# thrust_stand.net
KiCad netlist of a schematic drawn in EAGLE
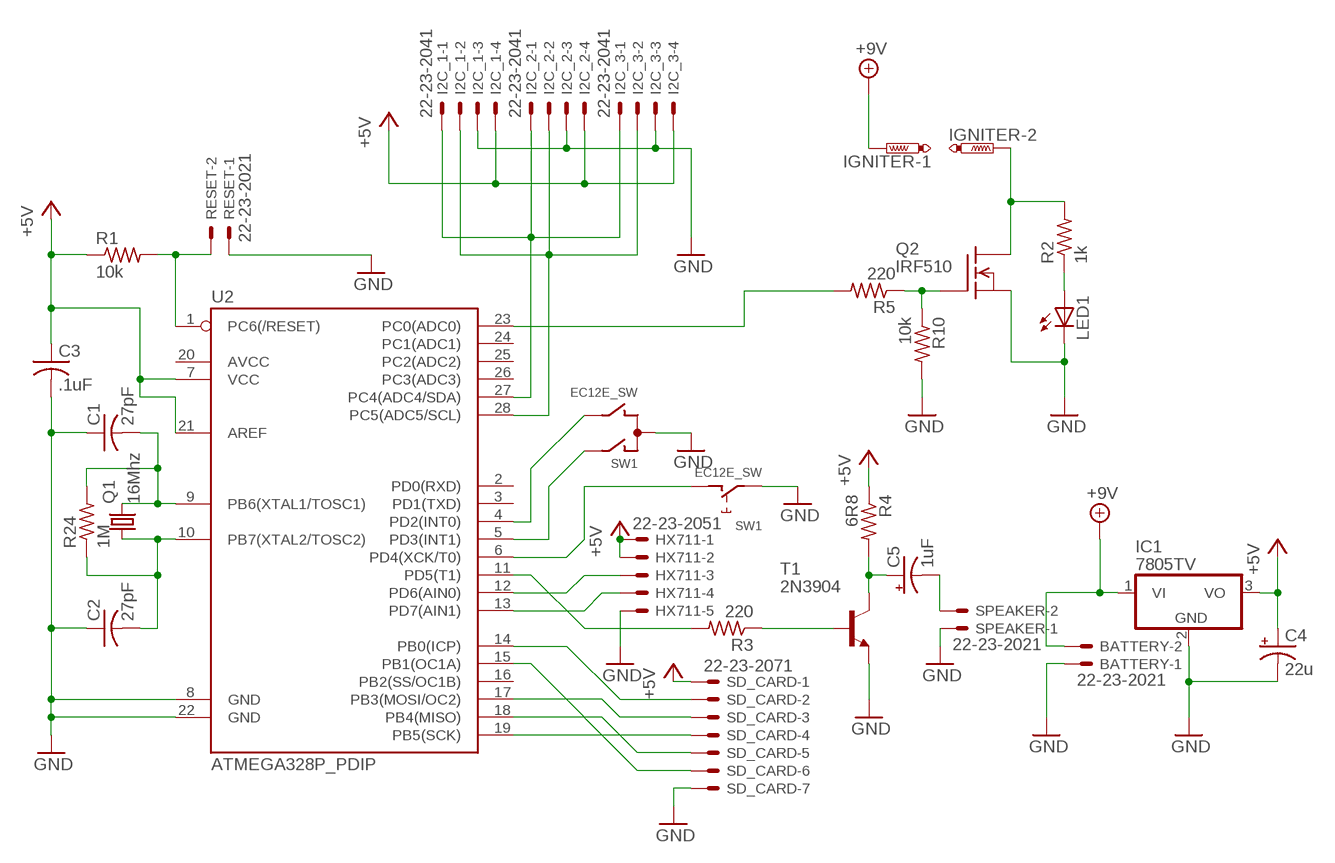
[diagram p0: schematic, sheet 1]

(export (version "E")
  (design (tool "Eeschema 10.0.6"))
  (components
    (comp (ref "BATTERY")
      (value "22-23-2021")
      (footprint "eagle-import:22-23-2021")
      (fields (field (name "MF") "MOLEX"))
      (libsource (lib "eagle-import") (part "22-23-2021"))
    )
    (comp (ref "C1")
      (value "27pF")
      (footprint "eagle-import:C025-040X050")
      (libsource (lib "eagle-import") (part "C-US025-040X050"))
    )
    (comp (ref "C2")
      (value "27pF")
      (footprint "eagle-import:C025-040X050")
      (libsource (lib "eagle-import") (part "C-US025-040X050"))
    )
    (comp (ref "C3")
      (value ".1uF")
      (footprint "eagle-import:C025-030X050")
      (libsource (lib "eagle-import") (part "C-US025-030X050"))
    )
    (comp (ref "C4")
      (value "22u")
      (footprint "eagle-import:B45181A")
      (libsource (lib "eagle-import") (part "CPOL-USB45181A"))
    )
    (comp (ref "C5")
      (value "1uF")
      (footprint "eagle-import:B45181A")
      (libsource (lib "eagle-import") (part "CPOL-USB45181A"))
    )
    (comp (ref "HX711")
      (value "22-23-2051")
      (footprint "eagle-import:22-23-2051")
      (fields (field (name "MF") "MOLEX"))
      (libsource (lib "eagle-import") (part "22-23-2051"))
    )
    (comp (ref "I2C_1")
      (value "22-23-2041")
      (footprint "eagle-import:22-23-2041")
      (fields (field (name "MF") "MOLEX"))
      (libsource (lib "eagle-import") (part "22-23-2041"))
    )
    (comp (ref "I2C_2")
      (value "22-23-2041")
      (footprint "eagle-import:22-23-2041")
      (fields (field (name "MF") "MOLEX"))
      (libsource (lib "eagle-import") (part "22-23-2041"))
    )
    (comp (ref "I2C_3")
      (value "22-23-2041")
      (footprint "eagle-import:22-23-2041")
      (fields (field (name "MF") "MOLEX"))
      (libsource (lib "eagle-import") (part "22-23-2041"))
    )
    (comp (ref "IC1")
      (value "7805TV")
      (footprint "eagle-import:TO220V")
      (libsource (lib "eagle-import") (part "78TV05"))
    )
    (comp (ref "IGNITER")
      (value "PTR2")
      (footprint "eagle-import:P2-38-17")
      (libsource (lib "eagle-import") (part "PTR2"))
    )
    (comp (ref "LED1")
      (value "LED5MM")
      (footprint "eagle-import:LED5MM")
      (libsource (lib "eagle-import") (part "LED5MM"))
    )
    (comp (ref "Q1")
      (value "16Mhz")
      (footprint "eagle-import:HC49_S")
      (libsource (lib "eagle-import") (part "CRYSTALHC49S"))
    )
    (comp (ref "Q2")
      (value "IRF510")
      (footprint "eagle-import:TO220")
      (libsource (lib "eagle-import") (part "IRF510"))
    )
    (comp (ref "R1")
      (value "10k")
      (footprint "eagle-import:0207_7")
      (libsource (lib "eagle-import") (part "R-US_0207/7"))
    )
    (comp (ref "R2")
      (value "1k")
      (footprint "eagle-import:0207_7")
      (libsource (lib "eagle-import") (part "R-US_0207/7"))
    )
    (comp (ref "R3")
      (value "220")
      (footprint "eagle-import:0207_7")
      (libsource (lib "eagle-import") (part "R-US_0207/7"))
    )
    (comp (ref "R4")
      (value "6R8")
      (footprint "eagle-import:0207_7")
      (libsource (lib "eagle-import") (part "R-US_0207/7"))
    )
    (comp (ref "R5")
      (value "220")
      (footprint "eagle-import:0309_10")
      (libsource (lib "eagle-import") (part "R-US_0309/10"))
    )
    (comp (ref "R10")
      (value "10k")
      (footprint "eagle-import:0207_7")
      (libsource (lib "eagle-import") (part "R-US_0207/7"))
    )
    (comp (ref "R24")
      (value "1M")
      (footprint "eagle-import:0207_7")
      (libsource (lib "eagle-import") (part "R-US_0207/7"))
    )
    (comp (ref "RESET")
      (value "22-23-2021")
      (footprint "eagle-import:22-23-2021")
      (fields (field (name "MF") "MOLEX"))
      (libsource (lib "eagle-import") (part "22-23-2021"))
    )
    (comp (ref "SD_CARD")
      (value "22-23-2071")
      (footprint "eagle-import:22-23-2071")
      (fields (field (name "MF") "MOLEX"))
      (libsource (lib "eagle-import") (part "22-23-2071"))
    )
    (comp (ref "SPEAKER")
      (value "22-23-2021")
      (footprint "eagle-import:22-23-2021")
      (fields (field (name "MF") "MOLEX"))
      (libsource (lib "eagle-import") (part "22-23-2021"))
    )
    (comp (ref "SW1")
      (value "EC12E_SW")
      (footprint "eagle-import:ALPS_EC12E_SW")
      (fields (field (name "MPN") "EC12E2424407"))
      (libsource (lib "eagle-import") (part "EC12E_SW"))
    )
    (comp (ref "T1")
      (value "2N3904")
      (footprint "eagle-import:TO92")
      (libsource (lib "eagle-import") (part "2N3904"))
    )
    (comp (ref "U2")
      (value "ATMEGA328P_PDIP")
      (footprint "eagle-import:DIL28-3")
      (libsource (lib "eagle-import") (part "ATMEGA328P_PDIP"))
    )
  )
  (nets
    (net (code "1") (name "+5V") (class "Default")
      (node (ref "C3") (pin "1") (pinfunction "1_1") (pintype "passive"))
      (node (ref "C4") (pin "+") (pinfunction "+_+") (pintype "passive"))
      (node (ref "HX711") (pin "1") (pinfunction "S_1") (pintype "passive"))
      (node (ref "HX711") (pin "2") (pinfunction "S_2") (pintype "passive"))
      (node (ref "I2C_1") (pin "4") (pinfunction "S_4") (pintype "passive"))
      (node (ref "I2C_2") (pin "4") (pinfunction "S_4") (pintype "passive"))
      (node (ref "I2C_3") (pin "4") (pinfunction "S_4") (pintype "passive"))
      (node (ref "IC1") (pin "3") (pinfunction "VO_3") (pintype "passive"))
      (node (ref "R1") (pin "1") (pinfunction "1_1") (pintype "passive"))
      (node (ref "R4") (pin "1") (pinfunction "1_1") (pintype "passive"))
      (node (ref "SD_CARD") (pin "1") (pinfunction "S_1") (pintype "passive"))
      (node (ref "U2") (pin "21") (pinfunction "AREF_21") (pintype "bidirectional"))
      (node (ref "U2") (pin "7") (pinfunction "VCC_7") (pintype "bidirectional"))
    )
    (net (code "2") (name "+9V") (class "Default")
      (node (ref "BATTERY") (pin "2") (pinfunction "S_2") (pintype "passive"))
      (node (ref "IC1") (pin "1") (pinfunction "VI_1") (pintype "input"))
      (node (ref "IGNITER") (pin "TP-1") (pinfunction "TP_TP-1") (pintype "input"))
    )
    (net (code "3") (name "GND") (class "Default")
      (node (ref "BATTERY") (pin "1") (pinfunction "S_1") (pintype "passive"))
      (node (ref "C1") (pin "1") (pinfunction "1_1") (pintype "passive"))
      (node (ref "C2") (pin "1") (pinfunction "1_1") (pintype "passive"))
      (node (ref "C3") (pin "2") (pinfunction "2_2") (pintype "passive"))
      (node (ref "C4") (pin "-") (pinfunction "-_-") (pintype "passive"))
      (node (ref "HX711") (pin "5") (pinfunction "S_5") (pintype "passive"))
      (node (ref "I2C_1") (pin "3") (pinfunction "S_3") (pintype "passive"))
      (node (ref "I2C_2") (pin "3") (pinfunction "S_3") (pintype "passive"))
      (node (ref "I2C_3") (pin "3") (pinfunction "S_3") (pintype "passive"))
      (node (ref "IC1") (pin "2") (pinfunction "GND_2") (pintype "passive"))
      (node (ref "LED1") (pin "K") (pinfunction "C_K") (pintype "passive"))
      (node (ref "Q2") (pin "3") (pinfunction "S_3") (pintype "passive"))
      (node (ref "R10") (pin "2") (pinfunction "2_2") (pintype "passive"))
      (node (ref "RESET") (pin "1") (pinfunction "S_1") (pintype "passive"))
      (node (ref "SD_CARD") (pin "7") (pinfunction "S_7") (pintype "passive"))
      (node (ref "SPEAKER") (pin "1") (pinfunction "S_1") (pintype "passive"))
      (node (ref "SW1") (pin "C") (pinfunction "C_C") (pintype "passive"))
      (node (ref "SW1") (pin "E") (pinfunction "2_E") (pintype "passive"))
      (node (ref "T1") (pin "3") (pinfunction "E_3") (pintype "passive"))
      (node (ref "U2") (pin "22") (pinfunction "GND_22") (pintype "bidirectional"))
      (node (ref "U2") (pin "8") (pinfunction "GND_8") (pintype "bidirectional"))
    )
    (net (code "4") (name "Net-(HX711C-S)") (class "Default")
      (node (ref "HX711") (pin "3") (pinfunction "S_3") (pintype "passive"))
      (node (ref "U2") (pin "12") (pinfunction "PD6(AIN0)_12") (pintype "bidirectional"))
    )
    (net (code "5") (name "Net-(HX711D-S)") (class "Default")
      (node (ref "HX711") (pin "4") (pinfunction "S_4") (pintype "passive"))
      (node (ref "U2") (pin "13") (pinfunction "PD7(AIN1)_13") (pintype "bidirectional"))
    )
    (net (code "6") (name "Net-(I2C_1A-S)") (class "Default")
      (node (ref "I2C_1") (pin "1") (pinfunction "S_1") (pintype "passive"))
      (node (ref "I2C_2") (pin "1") (pinfunction "S_1") (pintype "passive"))
      (node (ref "I2C_3") (pin "1") (pinfunction "S_1") (pintype "passive"))
      (node (ref "U2") (pin "27") (pinfunction "PC4(ADC4/SDA)_27") (pintype "bidirectional"))
    )
    (net (code "7") (name "Net-(I2C_1B-S)") (class "Default")
      (node (ref "I2C_1") (pin "2") (pinfunction "S_2") (pintype "passive"))
      (node (ref "I2C_2") (pin "2") (pinfunction "S_2") (pintype "passive"))
      (node (ref "I2C_3") (pin "2") (pinfunction "S_2") (pintype "passive"))
      (node (ref "U2") (pin "28") (pinfunction "PC5(ADC5/SCL)_28") (pintype "bidirectional"))
    )
    (net (code "8") (name "Net-(IGNITERB-TP)") (class "Default")
      (node (ref "IGNITER") (pin "TP-2") (pinfunction "TP_TP-2") (pintype "input"))
      (node (ref "Q2") (pin "2") (pinfunction "D_2") (pintype "passive"))
      (node (ref "R2") (pin "2") (pinfunction "2_2") (pintype "passive"))
    )
    (net (code "9") (name "Net-(LED1-PadA)") (class "Default")
      (node (ref "LED1") (pin "A") (pinfunction "A_A") (pintype "passive"))
      (node (ref "R2") (pin "1") (pinfunction "1_1") (pintype "passive"))
    )
    (net (code "10") (name "Net-(Q2-G)") (class "Default")
      (node (ref "Q2") (pin "1") (pinfunction "G_1") (pintype "passive"))
      (node (ref "R10") (pin "1") (pinfunction "1_1") (pintype "passive"))
      (node (ref "R5") (pin "1") (pinfunction "1_1") (pintype "passive"))
    )
    (net (code "11") (name "Net-(RESETB-S)") (class "Default")
      (node (ref "R1") (pin "2") (pinfunction "2_2") (pintype "passive"))
      (node (ref "RESET") (pin "2") (pinfunction "S_2") (pintype "passive"))
      (node (ref "U2") (pin "1") (pinfunction "PC6(/RESET)_1") (pintype "bidirectional"))
    )
    (net (code "12") (name "Net-(SD_CARDB-S)") (class "Default")
      (node (ref "SD_CARD") (pin "2") (pinfunction "S_2") (pintype "passive"))
      (node (ref "U2") (pin "14") (pinfunction "PB0(ICP)_14") (pintype "bidirectional"))
    )
    (net (code "13") (name "Net-(SD_CARDC-S)") (class "Default")
      (node (ref "SD_CARD") (pin "3") (pinfunction "S_3") (pintype "passive"))
      (node (ref "U2") (pin "17") (pinfunction "PB3(MOSI/OC2)_17") (pintype "bidirectional"))
    )
    (net (code "14") (name "Net-(SD_CARDD-S)") (class "Default")
      (node (ref "SD_CARD") (pin "4") (pinfunction "S_4") (pintype "passive"))
      (node (ref "U2") (pin "19") (pinfunction "PB5(SCK)_19") (pintype "bidirectional"))
    )
    (net (code "15") (name "Net-(SD_CARDE-S)") (class "Default")
      (node (ref "SD_CARD") (pin "5") (pinfunction "S_5") (pintype "passive"))
      (node (ref "U2") (pin "18") (pinfunction "PB4(MISO)_18") (pintype "bidirectional"))
    )
    (net (code "16") (name "Net-(SD_CARDF-S)") (class "Default")
      (node (ref "SD_CARD") (pin "6") (pinfunction "S_6") (pintype "passive"))
      (node (ref "U2") (pin "15") (pinfunction "PB1(OC1A)_15") (pintype "bidirectional"))
    )
    (net (code "17") (name "Net-(SPEAKERB-S)") (class "Default")
      (node (ref "C5") (pin "-") (pinfunction "-_-") (pintype "passive"))
      (node (ref "SPEAKER") (pin "2") (pinfunction "S_2") (pintype "passive"))
    )
    (net (code "18") (name "Net-(SW1B-1)") (class "Default")
      (node (ref "SW1") (pin "D") (pinfunction "1_D") (pintype "passive"))
      (node (ref "U2") (pin "6") (pinfunction "PD4(XCK/T0)_6") (pintype "bidirectional"))
    )
    (net (code "19") (name "Net-(T1-B)") (class "Default")
      (node (ref "R3") (pin "1") (pinfunction "1_1") (pintype "passive"))
      (node (ref "T1") (pin "2") (pinfunction "B_2") (pintype "passive"))
    )
    (net (code "20") (name "Net-(T1-C)") (class "Default")
      (node (ref "C5") (pin "+") (pinfunction "+_+") (pintype "passive"))
      (node (ref "R4") (pin "2") (pinfunction "2_2") (pintype "passive"))
      (node (ref "T1") (pin "1") (pinfunction "C_1") (pintype "passive"))
    )
    (net (code "21") (name "Net-(U2-PB6(XTAL1{slash}TOSC1))") (class "Default")
      (node (ref "C1") (pin "2") (pinfunction "2_2") (pintype "passive"))
      (node (ref "Q1") (pin "2") (pinfunction "2_2") (pintype "passive"))
      (node (ref "R24") (pin "2") (pinfunction "2_2") (pintype "passive"))
      (node (ref "U2") (pin "9") (pinfunction "PB6(XTAL1/TOSC1)_9") (pintype "bidirectional"))
    )
    (net (code "22") (name "Net-(U2-PB7(XTAL2{slash}TOSC2))") (class "Default")
      (node (ref "C2") (pin "2") (pinfunction "2_2") (pintype "passive"))
      (node (ref "Q1") (pin "1") (pinfunction "1_1") (pintype "passive"))
      (node (ref "R24") (pin "1") (pinfunction "1_1") (pintype "passive"))
      (node (ref "U2") (pin "10") (pinfunction "PB7(XTAL2/TOSC2)_10") (pintype "bidirectional"))
    )
    (net (code "23") (name "Net-(U2-PC0(ADC0))") (class "Default")
      (node (ref "R5") (pin "2") (pinfunction "2_2") (pintype "passive"))
      (node (ref "U2") (pin "23") (pinfunction "PC0(ADC0)_23") (pintype "bidirectional"))
    )
    (net (code "24") (name "Net-(U2-PD2(INT0))") (class "Default")
      (node (ref "SW1") (pin "B") (pinfunction "B_B") (pintype "passive"))
      (node (ref "U2") (pin "4") (pinfunction "PD2(INT0)_4") (pintype "bidirectional"))
    )
    (net (code "25") (name "Net-(U2-PD3(INT1))") (class "Default")
      (node (ref "SW1") (pin "A") (pinfunction "A_A") (pintype "passive"))
      (node (ref "U2") (pin "5") (pinfunction "PD3(INT1)_5") (pintype "bidirectional"))
    )
    (net (code "26") (name "Net-(U2-PD5(T1))") (class "Default")
      (node (ref "R3") (pin "2") (pinfunction "2_2") (pintype "passive"))
      (node (ref "U2") (pin "11") (pinfunction "PD5(T1)_11") (pintype "bidirectional"))
    )
    (net (code "27") (name "unconnected-(U2-AVCC-Pad20)") (class "Default")
      (node (ref "U2") (pin "20") (pinfunction "AVCC_20") (pintype "bidirectional"))
    )
    (net (code "28") (name "unconnected-(U2-PB2(SS{slash}OC1B)-Pad16)") (class "Default")
      (node (ref "U2") (pin "16") (pinfunction "PB2(SS/OC1B)_16") (pintype "bidirectional"))
    )
    (net (code "29") (name "unconnected-(U2-PC1(ADC1)-Pad24)") (class "Default")
      (node (ref "U2") (pin "24") (pinfunction "PC1(ADC1)_24") (pintype "bidirectional"))
    )
    (net (code "30") (name "unconnected-(U2-PC2(ADC2)-Pad25)") (class "Default")
      (node (ref "U2") (pin "25") (pinfunction "PC2(ADC2)_25") (pintype "bidirectional"))
    )
    (net (code "31") (name "unconnected-(U2-PC3(ADC3)-Pad26)") (class "Default")
      (node (ref "U2") (pin "26") (pinfunction "PC3(ADC3)_26") (pintype "bidirectional"))
    )
    (net (code "32") (name "unconnected-(U2-PD0(RXD)-Pad2)") (class "Default")
      (node (ref "U2") (pin "2") (pinfunction "PD0(RXD)_2") (pintype "bidirectional"))
    )
    (net (code "33") (name "unconnected-(U2-PD1(TXD)-Pad3)") (class "Default")
      (node (ref "U2") (pin "3") (pinfunction "PD1(TXD)_3") (pintype "bidirectional"))
    )
  )
)
